# aspirin.net
KiCad netlist of a schematic drawn in EAGLE
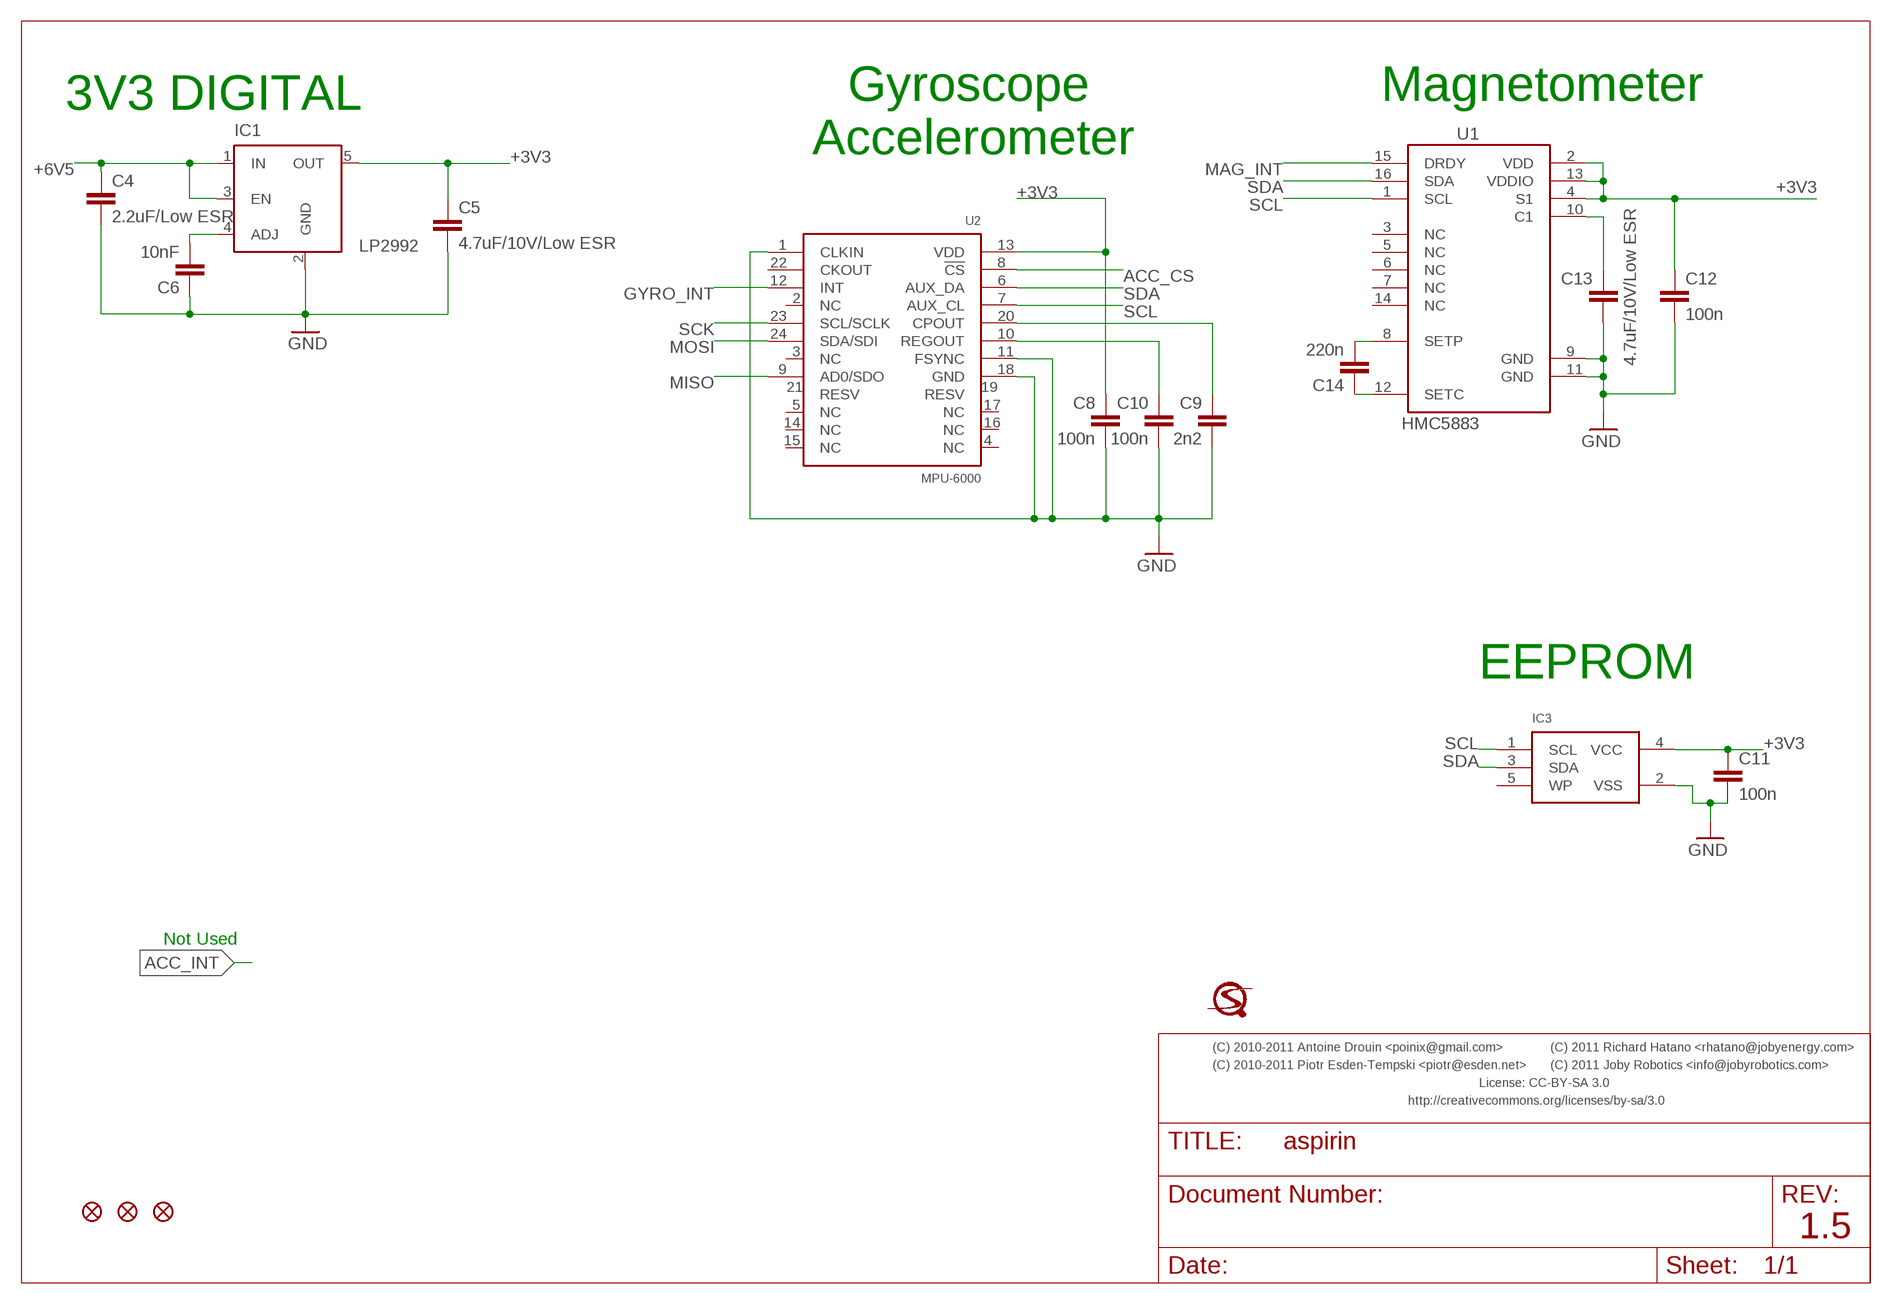
[diagram p0: schematic, sheet 1]

(export (version "E")
  (design (tool "Eeschema 10.0.6"))
  (components
    (comp (ref "C4")
      (value "2.2uF/Low ESR")
      (footprint "eagle-import:0603-CAP")
      (libsource (lib "eagle-import") (part "CAPACITOR-0603"))
    )
    (comp (ref "C5")
      (value "4.7uF/10V/Low ESR")
      (footprint "eagle-import:0402-CAP")
      (libsource (lib "eagle-import") (part "CAPACITOR-0402"))
    )
    (comp (ref "C6")
      (value "10nF")
      (footprint "eagle-import:0402-CAP")
      (libsource (lib "eagle-import") (part "CAPACITOR-0402"))
    )
    (comp (ref "C8")
      (value "100n")
      (footprint "eagle-import:0402-CAP")
      (libsource (lib "eagle-import") (part "CAPACITOR-0402"))
    )
    (comp (ref "C9")
      (value "2n2")
      (footprint "eagle-import:0402-CAP")
      (libsource (lib "eagle-import") (part "CAPACITOR-0402"))
    )
    (comp (ref "C10")
      (value "100n")
      (footprint "eagle-import:0402-CAP")
      (libsource (lib "eagle-import") (part "CAPACITOR-0402"))
    )
    (comp (ref "C11")
      (value "100n")
      (footprint "eagle-import:0402-CAP")
      (libsource (lib "eagle-import") (part "CAPACITOR-0402"))
    )
    (comp (ref "C12")
      (value "100n")
      (footprint "eagle-import:0402-CAP")
      (libsource (lib "eagle-import") (part "CAPACITOR-0402"))
    )
    (comp (ref "C13")
      (value "4.7uF/10V/Low ESR")
      (footprint "eagle-import:0402-CAP")
      (libsource (lib "eagle-import") (part "CAPACITOR-0402"))
    )
    (comp (ref "C14")
      (value "220n")
      (footprint "eagle-import:0402-CAP")
      (libsource (lib "eagle-import") (part "CAPACITOR-0402"))
    )
    (comp (ref "IC1")
      (value "LP2992")
      (footprint "eagle-import:SOT23-5")
      (libsource (lib "eagle-import") (part "MIC5219BM5"))
    )
    (comp (ref "IC3")
      (value "I2C_EEPROM-SOT23-5")
      (footprint "eagle-import:SOT23-5")
      (libsource (lib "eagle-import") (part "I2C_EEPROM-SOT23-5"))
    )
    (comp (ref "JP1")
      (value "FIDUCIAL1X2")
      (footprint "eagle-import:FIDUCIAL-1X2")
      (libsource (lib "eagle-import") (part "FIDUCIAL1X2"))
    )
    (comp (ref "JP2")
      (value "FIDUCIAL1X2")
      (footprint "eagle-import:FIDUCIAL-1X2")
      (libsource (lib "eagle-import") (part "FIDUCIAL1X2"))
    )
    (comp (ref "JP3")
      (value "FIDUCIAL1X2")
      (footprint "eagle-import:FIDUCIAL-1X2")
      (libsource (lib "eagle-import") (part "FIDUCIAL1X2"))
    )
    (comp (ref "U$2")
      (value "LOGO")
      (footprint "eagle-import:LOGO")
      (libsource (lib "eagle-import") (part "LOGO"))
    )
    (comp (ref "U1")
      (value "HMC5883")
      (footprint "eagle-import:PLCC16-HMC5883")
      (libsource (lib "eagle-import") (part "HMC5883"))
    )
    (comp (ref "U2")
      (value "MPU-6000")
      (footprint "eagle-import:QFN24-NO-PAD")
      (libsource (lib "eagle-import") (part "MPU-6000"))
    )
  )
  (nets
    (net (code "1") (name "/+3V3") (class "Default")
      (node (ref "C11") (pin "P$1") (pinfunction "1_P$1") (pintype "passive"))
      (node (ref "C12") (pin "P$1") (pinfunction "1_P$1") (pintype "passive"))
      (node (ref "C5") (pin "P$1") (pinfunction "1_P$1") (pintype "passive"))
      (node (ref "C8") (pin "P$1") (pinfunction "1_P$1") (pintype "passive"))
      (node (ref "IC1") (pin "5") (pinfunction "OUT_5") (pintype "output"))
      (node (ref "IC3") (pin "4") (pinfunction "VCC_4") (pintype "bidirectional"))
      (node (ref "U1") (pin "13") (pinfunction "VDDIO_13") (pintype "power_in"))
      (node (ref "U1") (pin "2") (pinfunction "VDD_2") (pintype "power_in"))
      (node (ref "U1") (pin "4") (pinfunction "S1_4") (pintype "power_in"))
      (node (ref "U2") (pin "13") (pinfunction "VDD_13") (pintype "bidirectional"))
    )
    (net (code "2") (name "/+6V5") (class "Default")
      (node (ref "C4") (pin "P$1") (pinfunction "1_P$1") (pintype "passive"))
      (node (ref "IC1") (pin "1") (pinfunction "IN_1") (pintype "input"))
      (node (ref "IC1") (pin "3") (pinfunction "EN_3") (pintype "input"))
    )
    (net (code "3") (name "/ACC_CS") (class "Default")
      (node (ref "U2") (pin "8") (pinfunction "~{CS}_8") (pintype "bidirectional"))
    )
    (net (code "4") (name "/GYRO_INT") (class "Default")
      (node (ref "U2") (pin "12") (pinfunction "INT_12") (pintype "bidirectional"))
    )
    (net (code "5") (name "/MAG_INT") (class "Default")
      (node (ref "U1") (pin "15") (pinfunction "DRDY_15") (pintype "bidirectional"))
    )
    (net (code "6") (name "/MISO") (class "Default")
      (node (ref "U2") (pin "9") (pinfunction "AD0/SDO_9") (pintype "bidirectional"))
    )
    (net (code "7") (name "/MOSI") (class "Default")
      (node (ref "U2") (pin "24") (pinfunction "SDA/SDI_24") (pintype "bidirectional"))
    )
    (net (code "8") (name "/SCK") (class "Default")
      (node (ref "U2") (pin "23") (pinfunction "SCL/SCLK_23") (pintype "bidirectional"))
    )
    (net (code "9") (name "/SCL") (class "Default")
      (node (ref "IC3") (pin "1") (pinfunction "SCL_1") (pintype "bidirectional"))
      (node (ref "U1") (pin "1") (pinfunction "SCL_1") (pintype "bidirectional"))
      (node (ref "U2") (pin "7") (pinfunction "AUX_CL_7") (pintype "bidirectional"))
    )
    (net (code "10") (name "/SDA") (class "Default")
      (node (ref "IC3") (pin "3") (pinfunction "SDA_3") (pintype "bidirectional"))
      (node (ref "U1") (pin "16") (pinfunction "SDA_16") (pintype "bidirectional"))
      (node (ref "U2") (pin "6") (pinfunction "AUX_DA_6") (pintype "bidirectional"))
    )
    (net (code "12") (name "GND") (class "Default")
      (node (ref "C10") (pin "P$2") (pinfunction "2_P$2") (pintype "passive"))
      (node (ref "C11") (pin "P$2") (pinfunction "2_P$2") (pintype "passive"))
      (node (ref "C12") (pin "P$2") (pinfunction "2_P$2") (pintype "passive"))
      (node (ref "C13") (pin "P$2") (pinfunction "2_P$2") (pintype "passive"))
      (node (ref "C4") (pin "P$2") (pinfunction "2_P$2") (pintype "passive"))
      (node (ref "C5") (pin "P$2") (pinfunction "2_P$2") (pintype "passive"))
      (node (ref "C6") (pin "P$1") (pinfunction "1_P$1") (pintype "passive"))
      (node (ref "C8") (pin "P$2") (pinfunction "2_P$2") (pintype "passive"))
      (node (ref "C9") (pin "P$2") (pinfunction "2_P$2") (pintype "passive"))
      (node (ref "IC1") (pin "2") (pinfunction "GND_2") (pintype "power_in"))
      (node (ref "IC3") (pin "2") (pinfunction "VSS_2") (pintype "bidirectional"))
      (node (ref "U1") (pin "11") (pinfunction "GND_11") (pintype "power_in"))
      (node (ref "U1") (pin "9") (pinfunction "GND_9") (pintype "power_in"))
      (node (ref "U2") (pin "1") (pinfunction "CLKIN_1") (pintype "bidirectional"))
      (node (ref "U2") (pin "11") (pinfunction "FSYNC_11") (pintype "bidirectional"))
      (node (ref "U2") (pin "18") (pinfunction "GND_18") (pintype "bidirectional"))
    )
    (net (code "13") (name "Net-(C6-2)") (class "Default")
      (node (ref "C6") (pin "P$2") (pinfunction "2_P$2") (pintype "passive"))
      (node (ref "IC1") (pin "4") (pinfunction "ADJ_4") (pintype "passive"))
    )
    (net (code "14") (name "Net-(C9-1)") (class "Default")
      (node (ref "C9") (pin "P$1") (pinfunction "1_P$1") (pintype "passive"))
      (node (ref "U2") (pin "20") (pinfunction "CPOUT_20") (pintype "bidirectional"))
    )
    (net (code "15") (name "Net-(C10-1)") (class "Default")
      (node (ref "C10") (pin "P$1") (pinfunction "1_P$1") (pintype "passive"))
      (node (ref "U2") (pin "10") (pinfunction "REGOUT_10") (pintype "bidirectional"))
    )
    (net (code "16") (name "Net-(C13-1)") (class "Default")
      (node (ref "C13") (pin "P$1") (pinfunction "1_P$1") (pintype "passive"))
      (node (ref "U1") (pin "10") (pinfunction "C1_10") (pintype "bidirectional"))
    )
    (net (code "17") (name "Net-(C14-1)") (class "Default")
      (node (ref "C14") (pin "P$1") (pinfunction "1_P$1") (pintype "passive"))
      (node (ref "U1") (pin "12") (pinfunction "SETC_12") (pintype "bidirectional"))
    )
    (net (code "18") (name "Net-(C14-2)") (class "Default")
      (node (ref "C14") (pin "P$2") (pinfunction "2_P$2") (pintype "passive"))
      (node (ref "U1") (pin "8") (pinfunction "SETP_8") (pintype "bidirectional"))
    )
    (net (code "19") (name "unconnected-(IC3-WP-Pad5)") (class "Default")
      (node (ref "IC3") (pin "5") (pinfunction "WP_5") (pintype "bidirectional"))
    )
    (net (code "20") (name "unconnected-(U1-NC-Pad3)") (class "Default")
      (node (ref "U1") (pin "3") (pinfunction "NC_3") (pintype "no_connect"))
    )
    (net (code "21") (name "unconnected-(U1-NC-Pad5)") (class "Default")
      (node (ref "U1") (pin "5") (pinfunction "NC_5") (pintype "no_connect"))
    )
    (net (code "22") (name "unconnected-(U1-NC-Pad6)") (class "Default")
      (node (ref "U1") (pin "6") (pinfunction "NC_6") (pintype "no_connect"))
    )
    (net (code "23") (name "unconnected-(U1-NC-Pad7)") (class "Default")
      (node (ref "U1") (pin "7") (pinfunction "NC_7") (pintype "no_connect"))
    )
    (net (code "24") (name "unconnected-(U1-NC-Pad14)") (class "Default")
      (node (ref "U1") (pin "14") (pinfunction "NC_14") (pintype "no_connect"))
    )
    (net (code "25") (name "unconnected-(U2-CKOUT-Pad22)") (class "Default")
      (node (ref "U2") (pin "22") (pinfunction "CKOUT_22") (pintype "bidirectional"))
    )
    (net (code "26") (name "unconnected-(U2-NC-Pad2)") (class "Default")
      (node (ref "U2") (pin "2") (pinfunction "NC_2") (pintype "bidirectional"))
    )
    (net (code "27") (name "unconnected-(U2-NC-Pad3)") (class "Default")
      (node (ref "U2") (pin "3") (pinfunction "NC_3") (pintype "bidirectional"))
    )
    (net (code "28") (name "unconnected-(U2-NC-Pad4)") (class "Default")
      (node (ref "U2") (pin "4") (pinfunction "NC_4") (pintype "bidirectional"))
    )
    (net (code "29") (name "unconnected-(U2-NC-Pad5)") (class "Default")
      (node (ref "U2") (pin "5") (pinfunction "NC_5") (pintype "bidirectional"))
    )
    (net (code "30") (name "unconnected-(U2-NC-Pad14)") (class "Default")
      (node (ref "U2") (pin "14") (pinfunction "NC_14") (pintype "bidirectional"))
    )
    (net (code "31") (name "unconnected-(U2-NC-Pad15)") (class "Default")
      (node (ref "U2") (pin "15") (pinfunction "NC_15") (pintype "bidirectional"))
    )
    (net (code "32") (name "unconnected-(U2-NC-Pad16)") (class "Default")
      (node (ref "U2") (pin "16") (pinfunction "NC_16") (pintype "bidirectional"))
    )
    (net (code "33") (name "unconnected-(U2-NC-Pad17)") (class "Default")
      (node (ref "U2") (pin "17") (pinfunction "NC_17") (pintype "bidirectional"))
    )
    (net (code "34") (name "unconnected-(U2-RESV-Pad19)") (class "Default")
      (node (ref "U2") (pin "19") (pinfunction "RESV_19") (pintype "bidirectional"))
    )
    (net (code "35") (name "unconnected-(U2-RESV-Pad21)") (class "Default")
      (node (ref "U2") (pin "21") (pinfunction "RESV_21") (pintype "bidirectional"))
    )
  )
)
